# Power_Supplies.net
KiCad netlist of a schematic drawn in Altium Designer
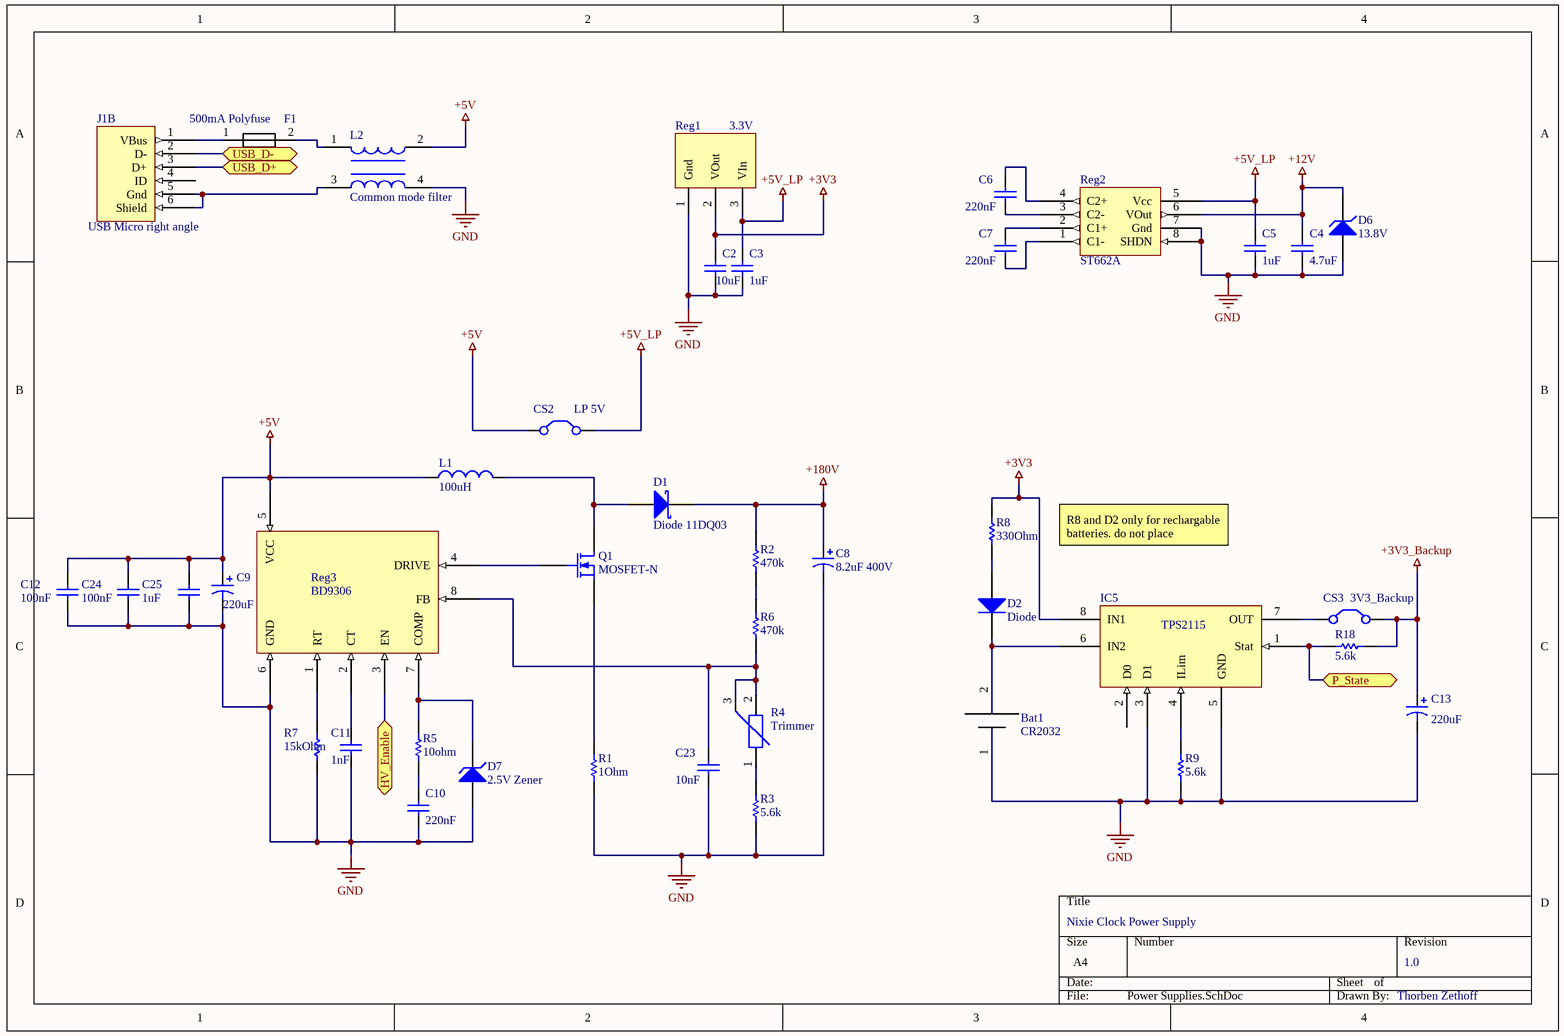
[diagram p0: Power Supplies.SchDoc]

(export (version "E")
  (design (tool "Eeschema 10.0.6"))
  (components
    (comp (ref "Bat1")
      (value "CR2032")
      (footprint "BU2032SM")
      (description "Battery")
      (libsource (lib "stdLib") (part "Battery"))
    )
    (comp (ref "C2")
      (value "10uF")
      (footprint "0603")
      (description "Capacitor")
      (fields (field (name "PUBLISHER") "Altium Limited"))
      (libsource (lib "Miscellaneous Devices") (part "Cap"))
    )
    (comp (ref "C3")
      (value "1uF")
      (footprint "0603")
      (description "Capacitor")
      (fields (field (name "PUBLISHER") "Altium Limited"))
      (libsource (lib "Miscellaneous Devices") (part "Cap"))
    )
    (comp (ref "C4")
      (value "4.7uF")
      (footprint "0603")
      (description "Capacitor")
      (fields (field (name "PUBLISHER") "Altium Limited"))
      (libsource (lib "Miscellaneous Devices") (part "Cap"))
    )
    (comp (ref "C5")
      (value "1uF")
      (footprint "0603")
      (description "Capacitor")
      (fields (field (name "PUBLISHER") "Altium Limited"))
      (libsource (lib "Miscellaneous Devices") (part "Cap"))
    )
    (comp (ref "C6")
      (value "220nF")
      (footprint "0603")
      (description "Capacitor")
      (fields (field (name "PUBLISHER") "Altium Limited"))
      (libsource (lib "Miscellaneous Devices") (part "Cap"))
    )
    (comp (ref "C7")
      (value "220nF")
      (footprint "0603")
      (description "Capacitor")
      (fields (field (name "PUBLISHER") "Altium Limited"))
      (libsource (lib "Miscellaneous Devices") (part "Cap"))
    )
    (comp (ref "C8")
      (value "8.2uF 400V")
      (footprint "10x10 SMD Electrolytic")
      (fields (field (name "PUBLISHER") "Altium Limited"))
      (libsource (lib "Miscellaneous Devices") (part "Cap Pol1"))
    )
    (comp (ref "C9")
      (value "220uF")
      (footprint "2917 Tantalum")
      (description "Tantalum")
      (fields (field (name "PUBLISHER") "Altium Limited"))
      (libsource (lib "Miscellaneous Devices") (part "Cap Pol1"))
    )
    (comp (ref "C10")
      (value "220nF")
      (footprint "0603")
      (description "Capacitor")
      (fields (field (name "PUBLISHER") "Altium Limited"))
      (libsource (lib "Miscellaneous Devices") (part "Cap"))
    )
    (comp (ref "C11")
      (value "1nF")
      (footprint "0603")
      (description "Capacitor")
      (fields (field (name "PUBLISHER") "Altium Limited"))
      (libsource (lib "Miscellaneous Devices") (part "Cap"))
    )
    (comp (ref "C12")
      (value "100nF")
      (footprint "0603")
      (description "Capacitor")
      (fields (field (name "PUBLISHER") "Altium Limited"))
      (libsource (lib "Miscellaneous Devices") (part "Cap"))
    )
    (comp (ref "C13")
      (value "220uF")
      (footprint "2917 Tantalum")
      (description "Tantalum")
      (fields (field (name "PUBLISHER") "Altium Limited"))
      (libsource (lib "Miscellaneous Devices") (part "Cap Pol1"))
    )
    (comp (ref "C23")
      (value "10nF")
      (footprint "0603")
      (description "Capacitor")
      (fields (field (name "PUBLISHER") "Altium Limited"))
      (libsource (lib "Miscellaneous Devices") (part "Cap"))
    )
    (comp (ref "C24")
      (value "100nF")
      (footprint "0603")
      (description "Capacitor")
      (fields (field (name "PUBLISHER") "Altium Limited"))
      (libsource (lib "Miscellaneous Devices") (part "Cap"))
    )
    (comp (ref "C25")
      (value "1uF")
      (footprint "0603")
      (description "Capacitor")
      (fields (field (name "PUBLISHER") "Altium Limited"))
      (libsource (lib "Miscellaneous Devices") (part "Cap"))
    )
    (comp (ref "CS2")
      (value "LP 5V")
      (footprint "Solder Jumper")
      (fields (field (name "PUBLISHER") "Altium Limited"))
      (libsource (lib "Miscellaneous Devices") (part "Jumper"))
    )
    (comp (ref "CS3")
      (value "3V3_Backup")
      (footprint "Solder Jumper")
      (description "I2C Passthrough")
      (fields (field (name "PUBLISHER") "Altium Limited"))
      (libsource (lib "Miscellaneous Devices") (part "Jumper"))
    )
    (comp (ref "D1")
      (value "Diode 11DQ03")
      (footprint "DO-214")
      (description "Schottky Rectifier")
      (fields (field (name "PUBLISHER") "Altium Limited"))
      (libsource (lib "Miscellaneous Devices") (part "Diode 11DQ03"))
    )
    (comp (ref "D2")
      (value "Diode")
      (footprint "SOD523")
      (description "Default Diode")
      (fields (field (name "PUBLISHER") "Altium Limited"))
      (libsource (lib "Miscellaneous Devices") (part "Diode"))
    )
    (comp (ref "D6")
      (value "13.8V")
      (footprint "SOD523")
      (description "Zener Diode")
      (fields (field (name "PUBLISHER") "Altium Limited"))
      (libsource (lib "Miscellaneous Devices") (part "D Zener"))
    )
    (comp (ref "D7")
      (value "2.5V Zener")
      (footprint "SOD523")
      (description "Zener Diode")
      (fields (field (name "PUBLISHER") "Altium Limited"))
      (libsource (lib "Miscellaneous Devices") (part "D Zener"))
    )
    (comp (ref "F1")
      (value "500mA Polyfuse")
      (footprint "0805")
      (description "Fuse OR PTC Resettable Fuse")
      (libsource (lib "stdLib") (part "Fuse"))
    )
    (comp (ref "IC5")
      (value "TPS2115")
      (footprint "VSON 3.1x3.1")
      (libsource (lib "stdLib") (part "TPS2115"))
    )
    (comp (ref "J1B")
      (value "USB Micro right angle")
      (footprint "USB 2.0 Type b micro")
      (libsource (lib "stdLib") (part "USB 2.0 Type B Micro"))
    )
    (comp (ref "L1")
      (value "100uH")
      (footprint "DR127 Eaton")
      (description "Inductor")
      (fields (field (name "PUBLISHER") "Altium Limited"))
      (libsource (lib "Miscellaneous Devices") (part "Inductor"))
    )
    (comp (ref "L2")
      (value "Common mode filter")
      (footprint "SON127P600 4 POS (8.50mm x 5.60mm)")
      (libsource (lib "stdLib") (part "Common mode filter"))
    )
    (comp (ref "Q1")
      (value "MOSFET-N")
      (footprint "TO252")
      (description "N-Channel MOSFET")
      (fields (field (name "PUBLISHER") "Altium Limited"))
      (libsource (lib "Miscellaneous Devices") (part "MOSFET-N"))
    )
    (comp (ref "R1")
      (value "1Ohm")
      (footprint "1206")
      (description "Resistor")
      (fields (field (name "PUBLISHER") "Altium Limited"))
      (libsource (lib "Miscellaneous Devices") (part "Res1"))
    )
    (comp (ref "R2")
      (value "470k")
      (footprint "1206")
      (description "Resistor")
      (fields (field (name "PUBLISHER") "Altium Limited"))
      (libsource (lib "Miscellaneous Devices") (part "Res1"))
    )
    (comp (ref "R3")
      (value "5.6k")
      (footprint "0603")
      (fields (field (name "PUBLISHER") "Altium Limited"))
      (libsource (lib "Miscellaneous Devices") (part "Res1"))
    )
    (comp (ref "R4")
      (value "Trimmer")
      (footprint "SM-42 Trimmer")
      (libsource (lib "stdLib") (part "Trimmer"))
    )
    (comp (ref "R5")
      (value "10ohm")
      (footprint "0603")
      (description "Resistor")
      (fields (field (name "PUBLISHER") "Altium Limited"))
      (libsource (lib "Miscellaneous Devices") (part "Res1"))
    )
    (comp (ref "R6")
      (value "470k")
      (footprint "1206")
      (description "Resistor")
      (fields (field (name "PUBLISHER") "Altium Limited"))
      (libsource (lib "Miscellaneous Devices") (part "Res1"))
    )
    (comp (ref "R7")
      (value "15kOhm")
      (footprint "0603")
      (description "Resistor")
      (fields (field (name "PUBLISHER") "Altium Limited"))
      (libsource (lib "Miscellaneous Devices") (part "Res1"))
    )
    (comp (ref "R8")
      (value "330Ohm")
      (footprint "0603")
      (description "Resistor")
      (fields (field (name "PUBLISHER") "Altium Limited"))
      (libsource (lib "Miscellaneous Devices") (part "Res1"))
    )
    (comp (ref "R9")
      (value "5.6k")
      (footprint "0603")
      (fields (field (name "PUBLISHER") "Altium Limited"))
      (libsource (lib "Miscellaneous Devices") (part "Res1"))
    )
    (comp (ref "R18")
      (value "5.6k")
      (footprint "0603")
      (fields (field (name "PUBLISHER") "Altium Limited"))
      (libsource (lib "Miscellaneous Devices") (part "Res1"))
    )
    (comp (ref "Reg1") (value "3.3V") (footprint "SOT223") (libsource (lib "stdLib") (part "VReg")))
    (comp (ref "Reg2")
      (value "ST662A")
      (footprint "SOIC8")
      (description "12V Boosting charge pump")
      (libsource (lib "stdLib") (part "ST662A"))
    )
    (comp (ref "Reg3") (value "BD9306") (footprint "MSOP8") (libsource (lib "stdLib") (part "BD9306")))
  )
  (nets
    (net (code "1") (name "+3V3") (class "Default")
      (node (ref "C2") (pin "1") (pinfunction "1_1") (pintype "passive"))
      (node (ref "IC5") (pin "8") (pinfunction "IN1_8") (pintype "power_in"))
      (node (ref "R8") (pin "1") (pinfunction "1_1") (pintype "passive"))
      (node (ref "Reg1") (pin "2") (pinfunction "VOut_2") (pintype "passive"))
    )
    (net (code "2") (name "+3V3_Backup") (class "Default")
      (node (ref "C13") (pin "1") (pinfunction "1_1") (pintype "passive"))
      (node (ref "CS3") (pin "2") (pinfunction "C2_2") (pintype "passive"))
      (node (ref "R18") (pin "1") (pinfunction "1_1") (pintype "passive"))
    )
    (net (code "3") (name "+5V") (class "Default")
      (node (ref "C12") (pin "1") (pinfunction "1_1") (pintype "passive"))
      (node (ref "C24") (pin "1") (pinfunction "1_1") (pintype "passive"))
      (node (ref "C25") (pin "1") (pinfunction "1_1") (pintype "passive"))
      (node (ref "C9") (pin "1") (pinfunction "1_1") (pintype "passive"))
      (node (ref "CS2") (pin "1") (pinfunction "C1_1") (pintype "passive"))
      (node (ref "L1") (pin "1") (pinfunction "1_1") (pintype "passive"))
      (node (ref "L2") (pin "2") (pinfunction "2_2") (pintype "passive"))
      (node (ref "Reg3") (pin "5") (pinfunction "VCC_5") (pintype "input"))
    )
    (net (code "4") (name "+5V_LP") (class "Default")
      (node (ref "C3") (pin "1") (pinfunction "1_1") (pintype "passive"))
      (node (ref "C5") (pin "1") (pinfunction "1_1") (pintype "passive"))
      (node (ref "CS2") (pin "2") (pinfunction "C2_2") (pintype "passive"))
      (node (ref "Reg1") (pin "3") (pinfunction "VIn_3") (pintype "passive"))
      (node (ref "Reg2") (pin "5") (pinfunction "Vcc_5") (pintype "power_in"))
    )
    (net (code "5") (name "+12V") (class "Default")
      (node (ref "C4") (pin "1") (pinfunction "1_1") (pintype "passive"))
      (node (ref "D6") (pin "2") (pinfunction "K_2") (pintype "passive"))
      (node (ref "Reg2") (pin "6") (pinfunction "VOut_6") (pintype "output"))
    )
    (net (code "6") (name "+180V") (class "Default")
      (node (ref "C8") (pin "1") (pinfunction "1_1") (pintype "passive"))
      (node (ref "D1") (pin "2") (pinfunction "K_2") (pintype "passive"))
      (node (ref "R2") (pin "1") (pinfunction "1_1") (pintype "passive"))
    )
    (net (code "7") (name "/HV_Enable") (class "Default")
      (node (ref "Reg3") (pin "3") (pinfunction "EN_3") (pintype "input"))
    )
    (net (code "8") (name "/P_State") (class "Default")
      (node (ref "IC5") (pin "1") (pinfunction "Stat_1") (pintype "input"))
      (node (ref "R18") (pin "2") (pinfunction "2_2") (pintype "passive"))
    )
    (net (code "9") (name "/USB_D+") (class "Default")
      (node (ref "J1B") (pin "3") (pinfunction "D+_3") (pintype "input"))
    )
    (net (code "10") (name "/USB_D-") (class "Default")
      (node (ref "J1B") (pin "2") (pinfunction "D-_2") (pintype "input"))
    )
    (net (code "11") (name "GND") (class "Default")
      (node (ref "Bat1") (pin "1") (pinfunction "-_1") (pintype "passive"))
      (node (ref "C10") (pin "2") (pinfunction "2_2") (pintype "passive"))
      (node (ref "C11") (pin "2") (pinfunction "2_2") (pintype "passive"))
      (node (ref "C12") (pin "2") (pinfunction "2_2") (pintype "passive"))
      (node (ref "C13") (pin "2") (pinfunction "2_2") (pintype "passive"))
      (node (ref "C2") (pin "2") (pinfunction "2_2") (pintype "passive"))
      (node (ref "C23") (pin "2") (pinfunction "2_2") (pintype "passive"))
      (node (ref "C24") (pin "2") (pinfunction "2_2") (pintype "passive"))
      (node (ref "C25") (pin "2") (pinfunction "2_2") (pintype "passive"))
      (node (ref "C3") (pin "2") (pinfunction "2_2") (pintype "passive"))
      (node (ref "C4") (pin "2") (pinfunction "2_2") (pintype "passive"))
      (node (ref "C5") (pin "2") (pinfunction "2_2") (pintype "passive"))
      (node (ref "C8") (pin "2") (pinfunction "2_2") (pintype "passive"))
      (node (ref "C9") (pin "2") (pinfunction "2_2") (pintype "passive"))
      (node (ref "D6") (pin "1") (pinfunction "A_1") (pintype "passive"))
      (node (ref "D7") (pin "1") (pinfunction "A_1") (pintype "passive"))
      (node (ref "IC5") (pin "3") (pinfunction "D1_3") (pintype "input"))
      (node (ref "IC5") (pin "5") (pinfunction "GND_5") (pintype "power_in"))
      (node (ref "L2") (pin "4") (pinfunction "2_4") (pintype "passive"))
      (node (ref "R1") (pin "2") (pinfunction "2_2") (pintype "passive"))
      (node (ref "R3") (pin "2") (pinfunction "2_2") (pintype "passive"))
      (node (ref "R7") (pin "2") (pinfunction "2_2") (pintype "passive"))
      (node (ref "R9") (pin "2") (pinfunction "2_2") (pintype "passive"))
      (node (ref "Reg1") (pin "1") (pinfunction "Gnd_1") (pintype "passive"))
      (node (ref "Reg2") (pin "7") (pinfunction "Gnd_7") (pintype "power_in"))
      (node (ref "Reg2") (pin "8") (pinfunction "SHDN_8") (pintype "input"))
      (node (ref "Reg3") (pin "6") (pinfunction "GND_6") (pintype "input"))
    )
    (net (code "12") (name "Net-(Bat1-+)") (class "Default")
      (node (ref "Bat1") (pin "2") (pinfunction "+_2") (pintype "passive"))
      (node (ref "D2") (pin "2") (pinfunction "K_2") (pintype "passive"))
      (node (ref "IC5") (pin "6") (pinfunction "IN2_6") (pintype "power_in"))
    )
    (net (code "13") (name "Net-(C10-Pad1)") (class "Default")
      (node (ref "C10") (pin "1") (pinfunction "1_1") (pintype "passive"))
      (node (ref "R5") (pin "2") (pinfunction "2_2") (pintype "passive"))
    )
    (net (code "14") (name "Net-(CS3-C1)") (class "Default")
      (node (ref "CS3") (pin "1") (pinfunction "C1_1") (pintype "passive"))
      (node (ref "IC5") (pin "7") (pinfunction "OUT_7") (pintype "power_in"))
    )
    (net (code "15") (name "Net-(D1-A)") (class "Default")
      (node (ref "D1") (pin "1") (pinfunction "A_1") (pintype "passive"))
      (node (ref "L1") (pin "2") (pinfunction "2_2") (pintype "passive"))
      (node (ref "Q1") (pin "1") (pinfunction "D_1") (pintype "passive"))
    )
    (net (code "16") (name "Net-(D2-A)") (class "Default")
      (node (ref "D2") (pin "1") (pinfunction "A_1") (pintype "passive"))
      (node (ref "R8") (pin "2") (pinfunction "2_2") (pintype "passive"))
    )
    (net (code "17") (name "Net-(D7-K)") (class "Default")
      (node (ref "D7") (pin "2") (pinfunction "K_2") (pintype "passive"))
      (node (ref "R5") (pin "1") (pinfunction "1_1") (pintype "passive"))
      (node (ref "Reg3") (pin "7") (pinfunction "COMP_7") (pintype "input"))
    )
    (net (code "18") (name "Net-(F1-Pad2)") (class "Default")
      (node (ref "F1") (pin "2") (pintype "passive"))
      (node (ref "L2") (pin "1") (pinfunction "1_1") (pintype "passive"))
    )
    (net (code "19") (name "Net-(IC5-ILim)") (class "Default")
      (node (ref "IC5") (pin "4") (pinfunction "ILim_4") (pintype "input"))
      (node (ref "R9") (pin "1") (pinfunction "1_1") (pintype "passive"))
    )
    (net (code "20") (name "Net-(J1B-Gnd)") (class "Default")
      (node (ref "J1B") (pin "5") (pinfunction "Gnd_5") (pintype "input"))
      (node (ref "J1B") (pin "6") (pinfunction "Shield_6") (pintype "input"))
      (node (ref "L2") (pin "3") (pinfunction "1_3") (pintype "passive"))
    )
    (net (code "21") (name "Net-(J1B-VBus)") (class "Default")
      (node (ref "F1") (pin "1") (pintype "passive"))
      (node (ref "J1B") (pin "1") (pinfunction "VBus_1") (pintype "output"))
    )
    (net (code "22") (name "Net-(Q1-G)") (class "Default")
      (node (ref "Q1") (pin "2") (pinfunction "G_2") (pintype "passive"))
      (node (ref "Reg3") (pin "4") (pinfunction "DRIVE_4") (pintype "input"))
    )
    (net (code "23") (name "Net-(Q1-S)") (class "Default")
      (node (ref "Q1") (pin "3") (pinfunction "S_3") (pintype "passive"))
      (node (ref "R1") (pin "1") (pinfunction "1_1") (pintype "passive"))
    )
    (net (code "24") (name "Net-(R2-Pad2)") (class "Default")
      (node (ref "R2") (pin "2") (pinfunction "2_2") (pintype "passive"))
      (node (ref "R6") (pin "1") (pinfunction "1_1") (pintype "passive"))
    )
    (net (code "25") (name "Net-(R3-Pad1)") (class "Default")
      (node (ref "R3") (pin "1") (pinfunction "1_1") (pintype "passive"))
      (node (ref "R4") (pin "1") (pintype "passive"))
    )
    (net (code "26") (name "Net-(Reg2-C1+)") (class "Default")
      (node (ref "C7") (pin "1") (pinfunction "1_1") (pintype "passive"))
      (node (ref "Reg2") (pin "2") (pinfunction "C1+_2") (pintype "output"))
    )
    (net (code "27") (name "Net-(Reg2-C1-)") (class "Default")
      (node (ref "C7") (pin "2") (pinfunction "2_2") (pintype "passive"))
      (node (ref "Reg2") (pin "1") (pinfunction "C1-_1") (pintype "output"))
    )
    (net (code "28") (name "Net-(Reg2-C2+)") (class "Default")
      (node (ref "C6") (pin "1") (pinfunction "1_1") (pintype "passive"))
      (node (ref "Reg2") (pin "4") (pinfunction "C2+_4") (pintype "output"))
    )
    (net (code "29") (name "Net-(Reg2-C2-)") (class "Default")
      (node (ref "C6") (pin "2") (pinfunction "2_2") (pintype "passive"))
      (node (ref "Reg2") (pin "3") (pinfunction "C2-_3") (pintype "output"))
    )
    (net (code "30") (name "Net-(Reg3-CT)") (class "Default")
      (node (ref "C11") (pin "1") (pinfunction "1_1") (pintype "passive"))
      (node (ref "Reg3") (pin "2") (pinfunction "CT_2") (pintype "input"))
    )
    (net (code "31") (name "Net-(Reg3-FB)") (class "Default")
      (node (ref "C23") (pin "1") (pinfunction "1_1") (pintype "passive"))
      (node (ref "R4") (pin "2") (pintype "passive"))
      (node (ref "R4") (pin "3") (pinfunction "3_3") (pintype "passive"))
      (node (ref "R6") (pin "2") (pinfunction "2_2") (pintype "passive"))
      (node (ref "Reg3") (pin "8") (pinfunction "FB_8") (pintype "input"))
    )
    (net (code "32") (name "Net-(Reg3-RT)") (class "Default")
      (node (ref "R7") (pin "1") (pinfunction "1_1") (pintype "passive"))
      (node (ref "Reg3") (pin "1") (pinfunction "RT_1") (pintype "input"))
    )
    (net (code "33") (name "unconnected-(IC5-D0-Pad2)") (class "Default")
      (node (ref "IC5") (pin "2") (pinfunction "D0_2") (pintype "input"))
    )
    (net (code "34") (name "unconnected-(J1B-ID-Pad4)") (class "Default")
      (node (ref "J1B") (pin "4") (pinfunction "ID_4") (pintype "input"))
    )
  )
)
